# AC2.net
KiCad netlist of a schematic drawn in EAGLE
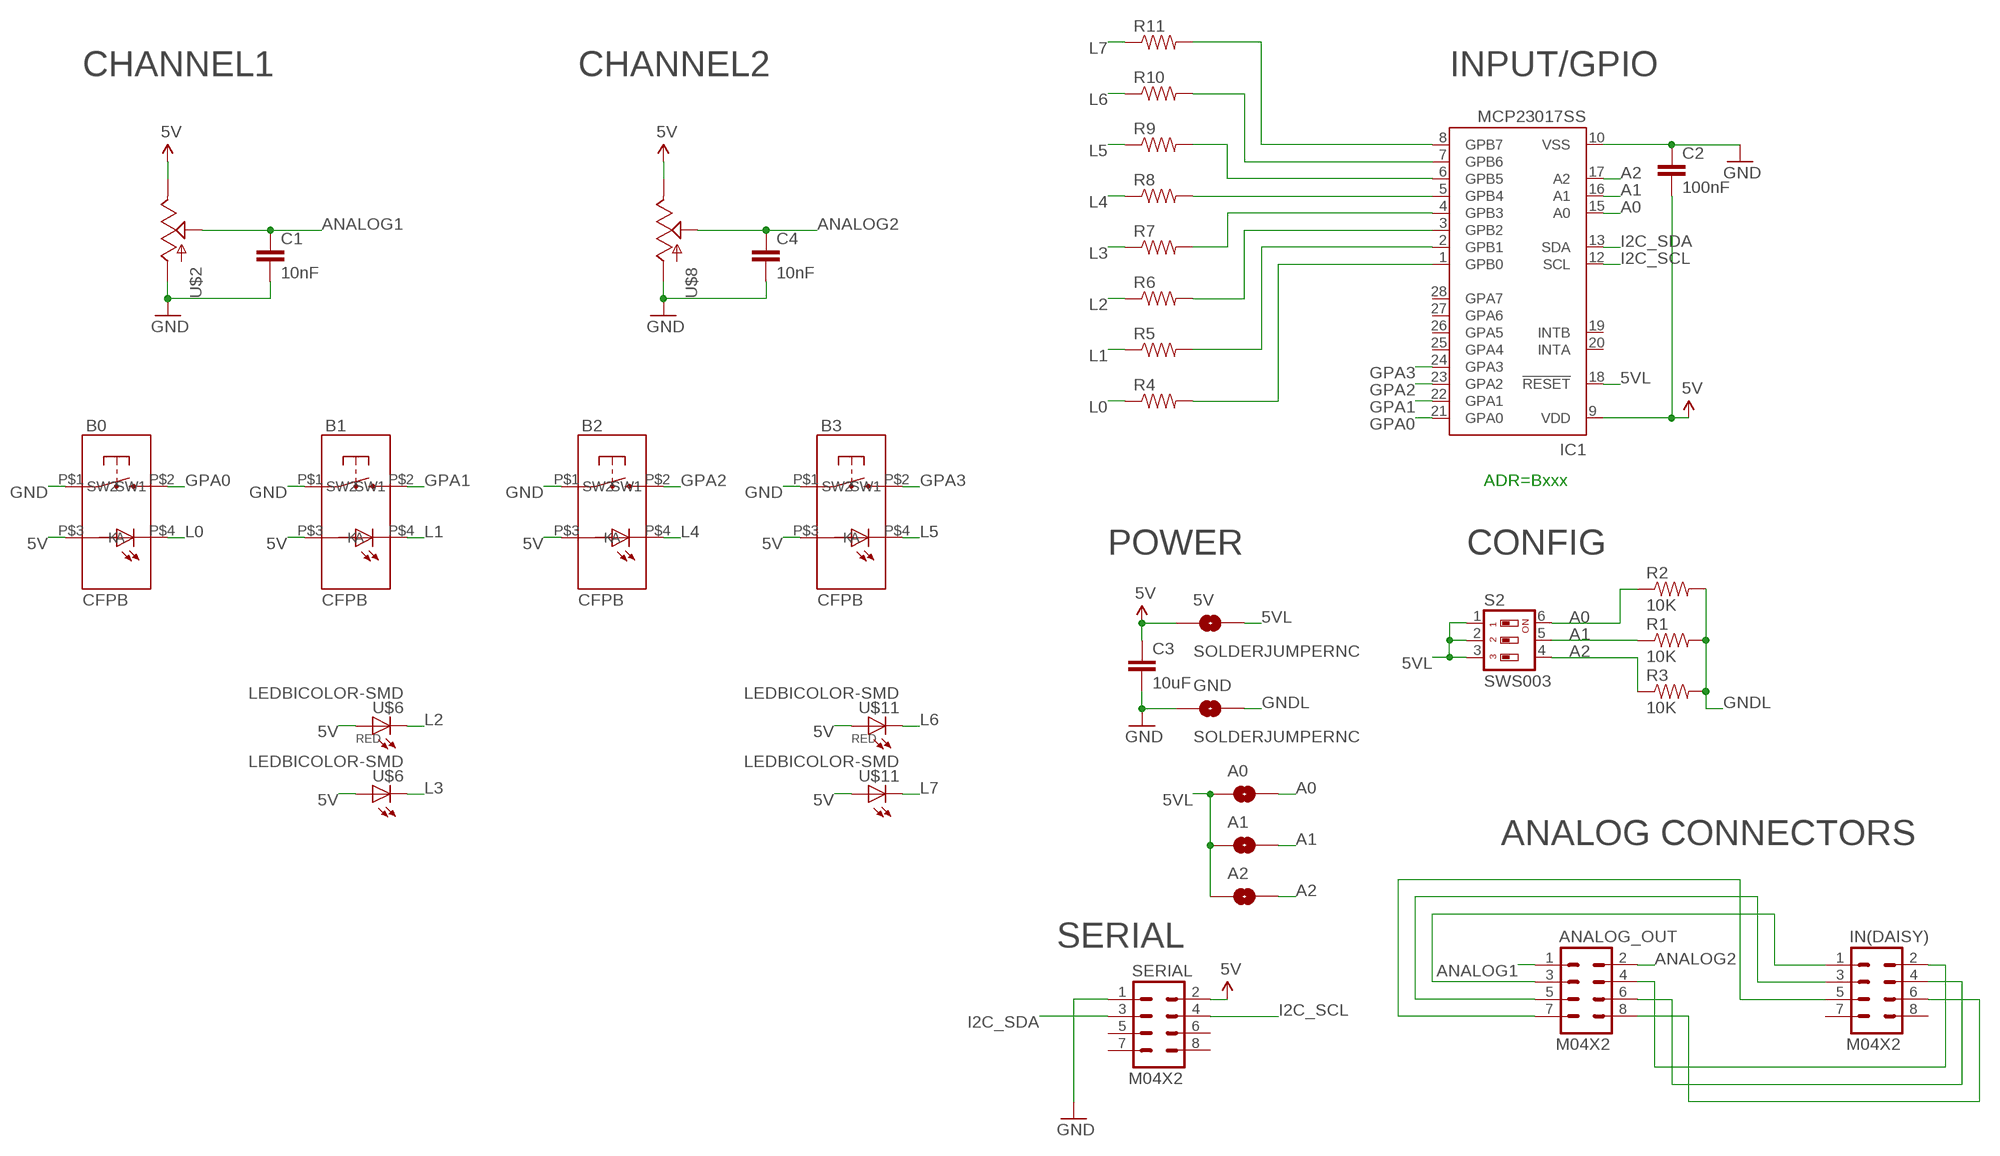
[diagram p0: schematic, sheet 1]

(export (version "E")
  (design (tool "Eeschema 10.0.6"))
  (components
    (comp (ref "5V")
      (value "SOLDERJUMPERNC")
      (footprint "eagle-import:SJ_2S")
      (libsource (lib "eagle-import") (part "SOLDERJUMPERNC"))
    )
    (comp (ref "A0")
      (value "SOLDERJUMPERNC")
      (footprint "eagle-import:SJ_2S")
      (libsource (lib "eagle-import") (part "SOLDERJUMPERNC"))
    )
    (comp (ref "A1")
      (value "SOLDERJUMPERNC")
      (footprint "eagle-import:SJ_2S")
      (libsource (lib "eagle-import") (part "SOLDERJUMPERNC"))
    )
    (comp (ref "A2")
      (value "SOLDERJUMPERNC")
      (footprint "eagle-import:SJ_2S")
      (libsource (lib "eagle-import") (part "SOLDERJUMPERNC"))
    )
    (comp (ref "ANALOG_OUT")
      (value "M04X2")
      (footprint "eagle-import:2X4")
      (libsource (lib "eagle-import") (part "M04X2"))
    )
    (comp (ref "B0")
      (value "CFPB")
      (footprint "eagle-import:CFPB-6_9MM")
      (libsource (lib "eagle-import") (part "CFPB"))
    )
    (comp (ref "B1")
      (value "CFPB")
      (footprint "eagle-import:CFPB-6_9MM")
      (libsource (lib "eagle-import") (part "CFPB"))
    )
    (comp (ref "B2")
      (value "CFPB")
      (footprint "eagle-import:CFPB-6_9MM")
      (libsource (lib "eagle-import") (part "CFPB"))
    )
    (comp (ref "B3")
      (value "CFPB")
      (footprint "eagle-import:CFPB-6_9MM")
      (libsource (lib "eagle-import") (part "CFPB"))
    )
    (comp (ref "C1")
      (value "10nF")
      (footprint "eagle-import:0603-CAP")
      (libsource (lib "eagle-import") (part "CAP0603-CAP"))
    )
    (comp (ref "C2")
      (value "100nF")
      (footprint "eagle-import:0603-CAP")
      (libsource (lib "eagle-import") (part "CAP0603-CAP"))
    )
    (comp (ref "C3")
      (value "10uF")
      (footprint "eagle-import:0805")
      (libsource (lib "eagle-import") (part "CAP0805"))
    )
    (comp (ref "C4")
      (value "10nF")
      (footprint "eagle-import:0603-CAP")
      (libsource (lib "eagle-import") (part "CAP0603-CAP"))
    )
    (comp (ref "GND")
      (value "SOLDERJUMPERNC")
      (footprint "eagle-import:SJ_2S")
      (libsource (lib "eagle-import") (part "SOLDERJUMPERNC"))
    )
    (comp (ref "IC1")
      (value "MCP23017SS")
      (footprint "eagle-import:SSOP28")
      (fields
        (field (name "MF") "MICROCHIP")
        (field (name "MPN") "MCP23017-E/SS")
        (field (name "MPN_1") "MCP23017-E/SS")
        (field (name "OC_FARNELL") "1467674")
        (field (name "OC_NEWARK") "31K2960")
      )
      (libsource (lib "eagle-import") (part "MCP23017SS"))
    )
    (comp (ref "IN(DAISY)")
      (value "M04X2")
      (footprint "eagle-import:2X4")
      (libsource (lib "eagle-import") (part "M04X2"))
    )
    (comp (ref "R1")
      (value "10K")
      (footprint "eagle-import:0603-RES")
      (libsource (lib "eagle-import") (part "RESISTOR0603-RES"))
    )
    (comp (ref "R2")
      (value "10K")
      (footprint "eagle-import:0603-RES")
      (libsource (lib "eagle-import") (part "RESISTOR0603-RES"))
    )
    (comp (ref "R3")
      (value "10K")
      (footprint "eagle-import:0603-RES")
      (libsource (lib "eagle-import") (part "RESISTOR0603-RES"))
    )
    (comp (ref "R4")
      (value "RESISTOR0603-RES")
      (footprint "eagle-import:0603-RES")
      (libsource (lib "eagle-import") (part "RESISTOR0603-RES"))
    )
    (comp (ref "R5")
      (value "RESISTOR0603-RES")
      (footprint "eagle-import:0603-RES")
      (libsource (lib "eagle-import") (part "RESISTOR0603-RES"))
    )
    (comp (ref "R6")
      (value "RESISTOR0603-RES")
      (footprint "eagle-import:0603-RES")
      (libsource (lib "eagle-import") (part "RESISTOR0603-RES"))
    )
    (comp (ref "R7")
      (value "RESISTOR0603-RES")
      (footprint "eagle-import:0603-RES")
      (libsource (lib "eagle-import") (part "RESISTOR0603-RES"))
    )
    (comp (ref "R8")
      (value "RESISTOR0603-RES")
      (footprint "eagle-import:0603-RES")
      (libsource (lib "eagle-import") (part "RESISTOR0603-RES"))
    )
    (comp (ref "R9")
      (value "RESISTOR0603-RES")
      (footprint "eagle-import:0603-RES")
      (libsource (lib "eagle-import") (part "RESISTOR0603-RES"))
    )
    (comp (ref "R10")
      (value "RESISTOR0603-RES")
      (footprint "eagle-import:0603-RES")
      (libsource (lib "eagle-import") (part "RESISTOR0603-RES"))
    )
    (comp (ref "R11")
      (value "RESISTOR0603-RES")
      (footprint "eagle-import:0603-RES")
      (libsource (lib "eagle-import") (part "RESISTOR0603-RES"))
    )
    (comp (ref "S2")
      (value "SWS003")
      (footprint "eagle-import:SMS-003")
      (libsource (lib "eagle-import") (part "SWS003"))
    )
    (comp (ref "SERIAL")
      (value "M04X2")
      (footprint "eagle-import:2X4")
      (libsource (lib "eagle-import") (part "M04X2"))
    )
    (comp (ref "U$2")
      (value "POT")
      (footprint "eagle-import:ALPS_POT")
      (libsource (lib "eagle-import") (part "POT"))
    )
    (comp (ref "U$6")
      (value "LEDBICOLOR-SMD")
      (footprint "eagle-import:LEDBICOLOR-SMD")
      (libsource (lib "eagle-import") (part "LEDBICOLOR-SMD"))
    )
    (comp (ref "U$8")
      (value "POT")
      (footprint "eagle-import:ALPS_POT")
      (libsource (lib "eagle-import") (part "POT"))
    )
    (comp (ref "U$11")
      (value "LEDBICOLOR-SMD")
      (footprint "eagle-import:LEDBICOLOR-SMD")
      (libsource (lib "eagle-import") (part "LEDBICOLOR-SMD"))
    )
  )
  (nets
    (net (code "1") (name "5V") (class "Default")
      (node (ref "5V") (pin "1") (pinfunction "1_1") (pintype "passive"))
      (node (ref "B0") (pin "P$3") (pinfunction "A_P$3") (pintype "bidirectional"))
      (node (ref "B1") (pin "P$3") (pinfunction "A_P$3") (pintype "bidirectional"))
      (node (ref "B2") (pin "P$3") (pinfunction "A_P$3") (pintype "bidirectional"))
      (node (ref "B3") (pin "P$3") (pinfunction "A_P$3") (pintype "bidirectional"))
      (node (ref "C2") (pin "2") (pinfunction "2_2") (pintype "passive"))
      (node (ref "C3") (pin "1") (pinfunction "1_1") (pintype "passive"))
      (node (ref "IC1") (pin "9") (pinfunction "VDD_9") (pintype "power_in"))
      (node (ref "SERIAL") (pin "2") (pinfunction "2_2") (pintype "passive"))
      (node (ref "U$11") (pin "P$1") (pinfunction "A_P$1") (pintype "passive"))
      (node (ref "U$11") (pin "P$3") (pinfunction "A1_P$3") (pintype "passive"))
      (node (ref "U$2") (pin "P$1") (pinfunction "E_P$1") (pintype "passive"))
      (node (ref "U$6") (pin "P$1") (pinfunction "A_P$1") (pintype "passive"))
      (node (ref "U$6") (pin "P$3") (pinfunction "A1_P$3") (pintype "passive"))
      (node (ref "U$8") (pin "P$1") (pinfunction "E_P$1") (pintype "passive"))
    )
    (net (code "2") (name "5VL") (class "Default")
      (node (ref "5V") (pin "2") (pinfunction "2_2") (pintype "passive"))
      (node (ref "A0") (pin "1") (pinfunction "1_1") (pintype "passive"))
      (node (ref "A1") (pin "1") (pinfunction "1_1") (pintype "passive"))
      (node (ref "A2") (pin "1") (pinfunction "1_1") (pintype "passive"))
      (node (ref "IC1") (pin "18") (pinfunction "~{RESET}_18") (pintype "input"))
      (node (ref "S2") (pin "1") (pinfunction "1_1") (pintype "passive"))
      (node (ref "S2") (pin "2") (pinfunction "2_2") (pintype "passive"))
      (node (ref "S2") (pin "3") (pinfunction "3_3") (pintype "passive"))
    )
    (net (code "3") (name "A0") (class "Default")
      (node (ref "A0") (pin "2") (pinfunction "2_2") (pintype "passive"))
      (node (ref "IC1") (pin "15") (pinfunction "A0_15") (pintype "input"))
      (node (ref "R2") (pin "1") (pinfunction "1_1") (pintype "passive"))
      (node (ref "S2") (pin "6") (pinfunction "6_6") (pintype "passive"))
    )
    (net (code "4") (name "A1") (class "Default")
      (node (ref "A1") (pin "2") (pinfunction "2_2") (pintype "passive"))
      (node (ref "IC1") (pin "16") (pinfunction "A1_16") (pintype "input"))
      (node (ref "R1") (pin "1") (pinfunction "1_1") (pintype "passive"))
      (node (ref "S2") (pin "5") (pinfunction "5_5") (pintype "passive"))
    )
    (net (code "5") (name "A2") (class "Default")
      (node (ref "A2") (pin "2") (pinfunction "2_2") (pintype "passive"))
      (node (ref "IC1") (pin "17") (pinfunction "A2_17") (pintype "input"))
      (node (ref "R3") (pin "1") (pinfunction "1_1") (pintype "passive"))
      (node (ref "S2") (pin "4") (pinfunction "4_4") (pintype "passive"))
    )
    (net (code "6") (name "ANALOG1") (class "Default")
      (node (ref "ANALOG_OUT") (pin "1") (pinfunction "1_1") (pintype "passive"))
      (node (ref "C1") (pin "1") (pinfunction "1_1") (pintype "passive"))
      (node (ref "U$2") (pin "P$2") (pinfunction "S_P$2") (pintype "passive"))
    )
    (net (code "7") (name "ANALOG2") (class "Default")
      (node (ref "ANALOG_OUT") (pin "2") (pinfunction "2_2") (pintype "passive"))
      (node (ref "C4") (pin "1") (pinfunction "1_1") (pintype "passive"))
      (node (ref "U$8") (pin "P$2") (pinfunction "S_P$2") (pintype "passive"))
    )
    (net (code "8") (name "GND") (class "Default")
      (node (ref "B0") (pin "P$1") (pinfunction "SW1_P$1") (pintype "bidirectional"))
      (node (ref "B1") (pin "P$1") (pinfunction "SW1_P$1") (pintype "bidirectional"))
      (node (ref "B2") (pin "P$1") (pinfunction "SW1_P$1") (pintype "bidirectional"))
      (node (ref "B3") (pin "P$1") (pinfunction "SW1_P$1") (pintype "bidirectional"))
      (node (ref "C1") (pin "2") (pinfunction "2_2") (pintype "passive"))
      (node (ref "C2") (pin "1") (pinfunction "1_1") (pintype "passive"))
      (node (ref "C3") (pin "2") (pinfunction "2_2") (pintype "passive"))
      (node (ref "C4") (pin "2") (pinfunction "2_2") (pintype "passive"))
      (node (ref "GND") (pin "1") (pinfunction "1_1") (pintype "passive"))
      (node (ref "IC1") (pin "10") (pinfunction "VSS_10") (pintype "power_in"))
      (node (ref "SERIAL") (pin "1") (pinfunction "1_1") (pintype "passive"))
      (node (ref "U$2") (pin "P$3") (pinfunction "A_P$3") (pintype "passive"))
      (node (ref "U$8") (pin "P$3") (pinfunction "A_P$3") (pintype "passive"))
    )
    (net (code "9") (name "GNDL") (class "Default")
      (node (ref "GND") (pin "2") (pinfunction "2_2") (pintype "passive"))
      (node (ref "R1") (pin "2") (pinfunction "2_2") (pintype "passive"))
      (node (ref "R2") (pin "2") (pinfunction "2_2") (pintype "passive"))
      (node (ref "R3") (pin "2") (pinfunction "2_2") (pintype "passive"))
    )
    (net (code "10") (name "GPA0") (class "Default")
      (node (ref "B0") (pin "P$2") (pinfunction "SW2_P$2") (pintype "bidirectional"))
      (node (ref "IC1") (pin "21") (pinfunction "GPA0_21") (pintype "bidirectional"))
    )
    (net (code "11") (name "GPA1") (class "Default")
      (node (ref "B1") (pin "P$2") (pinfunction "SW2_P$2") (pintype "bidirectional"))
      (node (ref "IC1") (pin "22") (pinfunction "GPA1_22") (pintype "bidirectional"))
    )
    (net (code "12") (name "GPA2") (class "Default")
      (node (ref "B2") (pin "P$2") (pinfunction "SW2_P$2") (pintype "bidirectional"))
      (node (ref "IC1") (pin "23") (pinfunction "GPA2_23") (pintype "bidirectional"))
    )
    (net (code "13") (name "GPA3") (class "Default")
      (node (ref "B3") (pin "P$2") (pinfunction "SW2_P$2") (pintype "bidirectional"))
      (node (ref "IC1") (pin "24") (pinfunction "GPA3_24") (pintype "bidirectional"))
    )
    (net (code "14") (name "I2C_SCL") (class "Default")
      (node (ref "IC1") (pin "12") (pinfunction "SCL_12") (pintype "input"))
      (node (ref "SERIAL") (pin "4") (pinfunction "4_4") (pintype "passive"))
    )
    (net (code "15") (name "I2C_SDA") (class "Default")
      (node (ref "IC1") (pin "13") (pinfunction "SDA_13") (pintype "bidirectional"))
      (node (ref "SERIAL") (pin "3") (pinfunction "3_3") (pintype "passive"))
    )
    (net (code "16") (name "L0") (class "Default")
      (node (ref "B0") (pin "P$4") (pinfunction "K_P$4") (pintype "bidirectional"))
      (node (ref "R4") (pin "1") (pinfunction "1_1") (pintype "passive"))
    )
    (net (code "17") (name "L1") (class "Default")
      (node (ref "B1") (pin "P$4") (pinfunction "K_P$4") (pintype "bidirectional"))
      (node (ref "R5") (pin "1") (pinfunction "1_1") (pintype "passive"))
    )
    (net (code "18") (name "L2") (class "Default")
      (node (ref "R6") (pin "1") (pinfunction "1_1") (pintype "passive"))
      (node (ref "U$6") (pin "P$2") (pinfunction "C_P$2") (pintype "passive"))
    )
    (net (code "19") (name "L3") (class "Default")
      (node (ref "R7") (pin "1") (pinfunction "1_1") (pintype "passive"))
      (node (ref "U$6") (pin "P$4") (pinfunction "C1_P$4") (pintype "passive"))
    )
    (net (code "20") (name "L4") (class "Default")
      (node (ref "B2") (pin "P$4") (pinfunction "K_P$4") (pintype "bidirectional"))
      (node (ref "R8") (pin "1") (pinfunction "1_1") (pintype "passive"))
    )
    (net (code "21") (name "L5") (class "Default")
      (node (ref "B3") (pin "P$4") (pinfunction "K_P$4") (pintype "bidirectional"))
      (node (ref "R9") (pin "1") (pinfunction "1_1") (pintype "passive"))
    )
    (net (code "22") (name "L6") (class "Default")
      (node (ref "R10") (pin "1") (pinfunction "1_1") (pintype "passive"))
      (node (ref "U$11") (pin "P$2") (pinfunction "C_P$2") (pintype "passive"))
    )
    (net (code "23") (name "L7") (class "Default")
      (node (ref "R11") (pin "1") (pinfunction "1_1") (pintype "passive"))
      (node (ref "U$11") (pin "P$4") (pinfunction "C1_P$4") (pintype "passive"))
    )
    (net (code "24") (name "Net-(ANALOG_OUT-Pad3)") (class "Default")
      (node (ref "ANALOG_OUT") (pin "3") (pinfunction "3_3") (pintype "passive"))
      (node (ref "IN(DAISY)") (pin "1") (pinfunction "1_1") (pintype "passive"))
    )
    (net (code "25") (name "Net-(ANALOG_OUT-Pad4)") (class "Default")
      (node (ref "ANALOG_OUT") (pin "4") (pinfunction "4_4") (pintype "passive"))
      (node (ref "IN(DAISY)") (pin "2") (pinfunction "2_2") (pintype "passive"))
    )
    (net (code "26") (name "Net-(ANALOG_OUT-Pad5)") (class "Default")
      (node (ref "ANALOG_OUT") (pin "5") (pinfunction "5_5") (pintype "passive"))
      (node (ref "IN(DAISY)") (pin "3") (pinfunction "3_3") (pintype "passive"))
    )
    (net (code "27") (name "Net-(ANALOG_OUT-Pad6)") (class "Default")
      (node (ref "ANALOG_OUT") (pin "6") (pinfunction "6_6") (pintype "passive"))
      (node (ref "IN(DAISY)") (pin "4") (pinfunction "4_4") (pintype "passive"))
    )
    (net (code "28") (name "Net-(ANALOG_OUT-Pad7)") (class "Default")
      (node (ref "ANALOG_OUT") (pin "7") (pinfunction "7_7") (pintype "passive"))
      (node (ref "IN(DAISY)") (pin "5") (pinfunction "5_5") (pintype "passive"))
    )
    (net (code "29") (name "Net-(ANALOG_OUT-Pad8)") (class "Default")
      (node (ref "ANALOG_OUT") (pin "8") (pinfunction "8_8") (pintype "passive"))
      (node (ref "IN(DAISY)") (pin "6") (pinfunction "6_6") (pintype "passive"))
    )
    (net (code "30") (name "Net-(IC1-GPB0)") (class "Default")
      (node (ref "IC1") (pin "1") (pinfunction "GPB0_1") (pintype "bidirectional"))
      (node (ref "R4") (pin "2") (pinfunction "2_2") (pintype "passive"))
    )
    (net (code "31") (name "Net-(IC1-GPB1)") (class "Default")
      (node (ref "IC1") (pin "2") (pinfunction "GPB1_2") (pintype "bidirectional"))
      (node (ref "R5") (pin "2") (pinfunction "2_2") (pintype "passive"))
    )
    (net (code "32") (name "Net-(IC1-GPB2)") (class "Default")
      (node (ref "IC1") (pin "3") (pinfunction "GPB2_3") (pintype "bidirectional"))
      (node (ref "R6") (pin "2") (pinfunction "2_2") (pintype "passive"))
    )
    (net (code "33") (name "Net-(IC1-GPB3)") (class "Default")
      (node (ref "IC1") (pin "4") (pinfunction "GPB3_4") (pintype "bidirectional"))
      (node (ref "R7") (pin "2") (pinfunction "2_2") (pintype "passive"))
    )
    (net (code "34") (name "Net-(IC1-GPB4)") (class "Default")
      (node (ref "IC1") (pin "5") (pinfunction "GPB4_5") (pintype "bidirectional"))
      (node (ref "R8") (pin "2") (pinfunction "2_2") (pintype "passive"))
    )
    (net (code "35") (name "Net-(IC1-GPB5)") (class "Default")
      (node (ref "IC1") (pin "6") (pinfunction "GPB5_6") (pintype "bidirectional"))
      (node (ref "R9") (pin "2") (pinfunction "2_2") (pintype "passive"))
    )
    (net (code "36") (name "Net-(IC1-GPB6)") (class "Default")
      (node (ref "IC1") (pin "7") (pinfunction "GPB6_7") (pintype "bidirectional"))
      (node (ref "R10") (pin "2") (pinfunction "2_2") (pintype "passive"))
    )
    (net (code "37") (name "Net-(IC1-GPB7)") (class "Default")
      (node (ref "IC1") (pin "8") (pinfunction "GPB7_8") (pintype "bidirectional"))
      (node (ref "R11") (pin "2") (pinfunction "2_2") (pintype "passive"))
    )
    (net (code "38") (name "unconnected-(IC1-GPA4-Pad25)") (class "Default")
      (node (ref "IC1") (pin "25") (pinfunction "GPA4_25") (pintype "bidirectional"))
    )
    (net (code "39") (name "unconnected-(IC1-GPA5-Pad26)") (class "Default")
      (node (ref "IC1") (pin "26") (pinfunction "GPA5_26") (pintype "bidirectional"))
    )
    (net (code "40") (name "unconnected-(IC1-GPA6-Pad27)") (class "Default")
      (node (ref "IC1") (pin "27") (pinfunction "GPA6_27") (pintype "bidirectional"))
    )
    (net (code "41") (name "unconnected-(IC1-GPA7-Pad28)") (class "Default")
      (node (ref "IC1") (pin "28") (pinfunction "GPA7_28") (pintype "bidirectional"))
    )
    (net (code "42") (name "unconnected-(IC1-INTA-Pad20)") (class "Default")
      (node (ref "IC1") (pin "20") (pinfunction "INTA_20") (pintype "output"))
    )
    (net (code "43") (name "unconnected-(IC1-INTB-Pad19)") (class "Default")
      (node (ref "IC1") (pin "19") (pinfunction "INTB_19") (pintype "output"))
    )
    (net (code "44") (name "unconnected-(IN(DAISY)-Pad7)") (class "Default")
      (node (ref "IN(DAISY)") (pin "7") (pinfunction "7_7") (pintype "passive"))
    )
    (net (code "45") (name "unconnected-(IN(DAISY)-Pad8)") (class "Default")
      (node (ref "IN(DAISY)") (pin "8") (pinfunction "8_8") (pintype "passive"))
    )
    (net (code "46") (name "unconnected-(SERIAL-Pad5)") (class "Default")
      (node (ref "SERIAL") (pin "5") (pinfunction "5_5") (pintype "passive"))
    )
    (net (code "47") (name "unconnected-(SERIAL-Pad6)") (class "Default")
      (node (ref "SERIAL") (pin "6") (pinfunction "6_6") (pintype "passive"))
    )
    (net (code "48") (name "unconnected-(SERIAL-Pad7)") (class "Default")
      (node (ref "SERIAL") (pin "7") (pinfunction "7_7") (pintype "passive"))
    )
    (net (code "49") (name "unconnected-(SERIAL-Pad8)") (class "Default")
      (node (ref "SERIAL") (pin "8") (pinfunction "8_8") (pintype "passive"))
    )
  )
)
